# Heart-shaped-LED.net
KiCad netlist of a schematic drawn in EAGLE
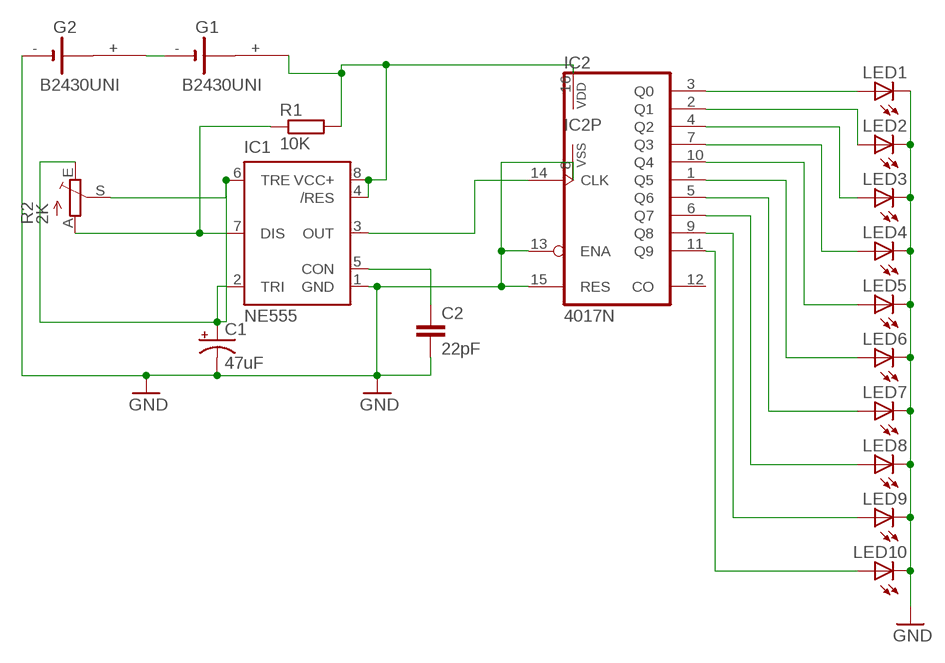
[diagram p0: schematic, sheet 1]

(export (version "E")
  (design (tool "Eeschema 10.0.6"))
  (components
    (comp (ref "C1")
      (value "47uF")
      (footprint "eagle-import:B45181A")
      (libsource (lib "eagle-import") (part "CPOL-USB45181A"))
    )
    (comp (ref "C2")
      (value "22pF")
      (footprint "eagle-import:C025-024X044")
      (libsource (lib "eagle-import") (part "C-EU025-024X044"))
    )
    (comp (ref "G1")
      (value "B2430UNI")
      (footprint "eagle-import:B2430UNI")
      (libsource (lib "eagle-import") (part "B2430UNI"))
    )
    (comp (ref "G2")
      (value "B2430UNI")
      (footprint "eagle-import:B2430UNI")
      (libsource (lib "eagle-import") (part "B2430UNI"))
    )
    (comp (ref "IC1")
      (value "NE555")
      (footprint "eagle-import:DIL-08")
      (fields (field (name "MF") "Arrow Electronics") (field (name "MPN") "NE555N"))
      (libsource (lib "eagle-import") (part "NE555"))
    )
    (comp (ref "IC2")
      (value "4017N")
      (footprint "eagle-import:DIL16")
      (fields (field (name "SPICEPREFIX") "X"))
      (libsource (lib "eagle-import") (part "4017N"))
    )
    (comp (ref "LED1")
      (value "LED5MM")
      (footprint "eagle-import:LED5MM")
      (libsource (lib "eagle-import") (part "LED5MM"))
    )
    (comp (ref "LED2")
      (value "LED5MM")
      (footprint "eagle-import:LED5MM")
      (libsource (lib "eagle-import") (part "LED5MM"))
    )
    (comp (ref "LED3")
      (value "LED5MM")
      (footprint "eagle-import:LED5MM")
      (libsource (lib "eagle-import") (part "LED5MM"))
    )
    (comp (ref "LED4")
      (value "LED5MM")
      (footprint "eagle-import:LED5MM")
      (libsource (lib "eagle-import") (part "LED5MM"))
    )
    (comp (ref "LED5")
      (value "LED5MM")
      (footprint "eagle-import:LED5MM")
      (libsource (lib "eagle-import") (part "LED5MM"))
    )
    (comp (ref "LED6")
      (value "LED5MM")
      (footprint "eagle-import:LED5MM")
      (libsource (lib "eagle-import") (part "LED5MM"))
    )
    (comp (ref "LED7")
      (value "LED5MM")
      (footprint "eagle-import:LED5MM")
      (libsource (lib "eagle-import") (part "LED5MM"))
    )
    (comp (ref "LED8")
      (value "LED5MM")
      (footprint "eagle-import:LED5MM")
      (libsource (lib "eagle-import") (part "LED5MM"))
    )
    (comp (ref "LED9")
      (value "LED5MM")
      (footprint "eagle-import:LED5MM")
      (libsource (lib "eagle-import") (part "LED5MM"))
    )
    (comp (ref "LED10")
      (value "LED5MM")
      (footprint "eagle-import:LED5MM")
      (libsource (lib "eagle-import") (part "LED5MM"))
    )
    (comp (ref "R1")
      (value "10K")
      (footprint "eagle-import:0207_7")
      (libsource (lib "eagle-import") (part "R-EU_0207/7"))
    )
    (comp (ref "R2")
      (value "2K")
      (footprint "eagle-import:CA9V")
      (libsource (lib "eagle-import") (part "TRIM_EU-CA9V"))
    )
  )
  (nets
    (net (code "1") (name "GND") (class "Default")
      (node (ref "C1") (pin "-") (pinfunction "-_-") (pintype "passive"))
      (node (ref "C2") (pin "2") (pinfunction "2_2") (pintype "passive"))
      (node (ref "G2") (pin "-") (pinfunction "-_-") (pintype "passive"))
      (node (ref "IC1") (pin "1") (pinfunction "GND_1") (pintype "power_in"))
      (node (ref "IC2") (pin "13") (pinfunction "ENA_13") (pintype "input"))
      (node (ref "IC2") (pin "15") (pinfunction "RES_15") (pintype "input"))
      (node (ref "IC2") (pin "8") (pinfunction "VSS_8") (pintype "power_in"))
      (node (ref "LED1") (pin "K") (pinfunction "C_K") (pintype "passive"))
      (node (ref "LED10") (pin "K") (pinfunction "C_K") (pintype "passive"))
      (node (ref "LED2") (pin "K") (pinfunction "C_K") (pintype "passive"))
      (node (ref "LED3") (pin "K") (pinfunction "C_K") (pintype "passive"))
      (node (ref "LED4") (pin "K") (pinfunction "C_K") (pintype "passive"))
      (node (ref "LED5") (pin "K") (pinfunction "C_K") (pintype "passive"))
      (node (ref "LED6") (pin "K") (pinfunction "C_K") (pintype "passive"))
      (node (ref "LED7") (pin "K") (pinfunction "C_K") (pintype "passive"))
      (node (ref "LED8") (pin "K") (pinfunction "C_K") (pintype "passive"))
      (node (ref "LED9") (pin "K") (pinfunction "C_K") (pintype "passive"))
    )
    (net (code "2") (name "Net-(G1-Pad-)") (class "Default")
      (node (ref "G1") (pin "-") (pinfunction "-_-") (pintype "passive"))
      (node (ref "G2") (pin "+") (pinfunction "+_+") (pintype "passive"))
    )
    (net (code "3") (name "Net-(IC1-CON)") (class "Default")
      (node (ref "C2") (pin "1") (pinfunction "1_1") (pintype "passive"))
      (node (ref "IC1") (pin "5") (pinfunction "CON_5") (pintype "input"))
    )
    (net (code "4") (name "Net-(IC1-DIS)") (class "Default")
      (node (ref "IC1") (pin "7") (pinfunction "DIS_7") (pintype "input"))
      (node (ref "R1") (pin "1") (pinfunction "1_1") (pintype "passive"))
      (node (ref "R2") (pin "A") (pinfunction "A_A") (pintype "passive"))
    )
    (net (code "5") (name "Net-(IC1-OUT)") (class "Default")
      (node (ref "IC1") (pin "3") (pinfunction "OUT_3") (pintype "output"))
      (node (ref "IC2") (pin "14") (pinfunction "CLK_14") (pintype "input"))
    )
    (net (code "6") (name "Net-(IC1-TRE)") (class "Default")
      (node (ref "C1") (pin "+") (pinfunction "+_+") (pintype "passive"))
      (node (ref "IC1") (pin "2") (pinfunction "TRI_2") (pintype "input"))
      (node (ref "IC1") (pin "6") (pinfunction "TRE_6") (pintype "input"))
      (node (ref "R2") (pin "E") (pinfunction "E_E") (pintype "passive"))
      (node (ref "R2") (pin "S") (pinfunction "S_S") (pintype "passive"))
    )
    (net (code "7") (name "Net-(IC1-VCC+)") (class "Default")
      (node (ref "G1") (pin "+") (pinfunction "+_+") (pintype "passive"))
      (node (ref "IC1") (pin "4") (pinfunction "/RES_4") (pintype "input"))
      (node (ref "IC1") (pin "8") (pinfunction "VCC+_8") (pintype "power_in"))
      (node (ref "IC2") (pin "16") (pinfunction "VDD_16") (pintype "power_in"))
      (node (ref "R1") (pin "2") (pinfunction "2_2") (pintype "passive"))
    )
    (net (code "8") (name "Net-(IC2A-Q0)") (class "Default")
      (node (ref "IC2") (pin "3") (pinfunction "Q0_3") (pintype "output"))
      (node (ref "LED1") (pin "A") (pinfunction "A_A") (pintype "passive"))
    )
    (net (code "9") (name "Net-(IC2A-Q1)") (class "Default")
      (node (ref "IC2") (pin "2") (pinfunction "Q1_2") (pintype "output"))
      (node (ref "LED2") (pin "A") (pinfunction "A_A") (pintype "passive"))
    )
    (net (code "10") (name "Net-(IC2A-Q2)") (class "Default")
      (node (ref "IC2") (pin "4") (pinfunction "Q2_4") (pintype "output"))
      (node (ref "LED3") (pin "A") (pinfunction "A_A") (pintype "passive"))
    )
    (net (code "11") (name "Net-(IC2A-Q3)") (class "Default")
      (node (ref "IC2") (pin "7") (pinfunction "Q3_7") (pintype "output"))
      (node (ref "LED4") (pin "A") (pinfunction "A_A") (pintype "passive"))
    )
    (net (code "12") (name "Net-(IC2A-Q4)") (class "Default")
      (node (ref "IC2") (pin "10") (pinfunction "Q4_10") (pintype "output"))
      (node (ref "LED5") (pin "A") (pinfunction "A_A") (pintype "passive"))
    )
    (net (code "13") (name "Net-(IC2A-Q5)") (class "Default")
      (node (ref "IC2") (pin "1") (pinfunction "Q5_1") (pintype "output"))
      (node (ref "LED6") (pin "A") (pinfunction "A_A") (pintype "passive"))
    )
    (net (code "14") (name "Net-(IC2A-Q6)") (class "Default")
      (node (ref "IC2") (pin "5") (pinfunction "Q6_5") (pintype "output"))
      (node (ref "LED7") (pin "A") (pinfunction "A_A") (pintype "passive"))
    )
    (net (code "15") (name "Net-(IC2A-Q7)") (class "Default")
      (node (ref "IC2") (pin "6") (pinfunction "Q7_6") (pintype "output"))
      (node (ref "LED8") (pin "A") (pinfunction "A_A") (pintype "passive"))
    )
    (net (code "16") (name "Net-(IC2A-Q8)") (class "Default")
      (node (ref "IC2") (pin "9") (pinfunction "Q8_9") (pintype "output"))
      (node (ref "LED9") (pin "A") (pinfunction "A_A") (pintype "passive"))
    )
    (net (code "17") (name "Net-(IC2A-Q9)") (class "Default")
      (node (ref "IC2") (pin "11") (pinfunction "Q9_11") (pintype "output"))
      (node (ref "LED10") (pin "A") (pinfunction "A_A") (pintype "passive"))
    )
    (net (code "18") (name "unconnected-(G1-+-Pad+@1)") (class "Default")
      (node (ref "G1") (pin "+@1") (pinfunction "+_+@1") (pintype "passive"))
    )
    (net (code "19") (name "unconnected-(G1-+-Pad+@2)") (class "Default")
      (node (ref "G1") (pin "+@2") (pinfunction "+_+@2") (pintype "passive"))
    )
    (net (code "20") (name "unconnected-(G1-+-Pad+@3)") (class "Default")
      (node (ref "G1") (pin "+@3") (pinfunction "+_+@3") (pintype "passive"))
    )
    (net (code "21") (name "unconnected-(G1-+-Pad+@4)") (class "Default")
      (node (ref "G1") (pin "+@4") (pinfunction "+_+@4") (pintype "passive"))
    )
    (net (code "22") (name "unconnected-(G1---Pad-@1)") (class "Default")
      (node (ref "G1") (pin "-@1") (pinfunction "-_-@1") (pintype "passive"))
    )
    (net (code "23") (name "unconnected-(G2-+-Pad+@1)") (class "Default")
      (node (ref "G2") (pin "+@1") (pinfunction "+_+@1") (pintype "passive"))
    )
    (net (code "24") (name "unconnected-(G2-+-Pad+@2)") (class "Default")
      (node (ref "G2") (pin "+@2") (pinfunction "+_+@2") (pintype "passive"))
    )
    (net (code "25") (name "unconnected-(G2-+-Pad+@3)") (class "Default")
      (node (ref "G2") (pin "+@3") (pinfunction "+_+@3") (pintype "passive"))
    )
    (net (code "26") (name "unconnected-(G2-+-Pad+@4)") (class "Default")
      (node (ref "G2") (pin "+@4") (pinfunction "+_+@4") (pintype "passive"))
    )
    (net (code "27") (name "unconnected-(G2---Pad-@1)") (class "Default")
      (node (ref "G2") (pin "-@1") (pinfunction "-_-@1") (pintype "passive"))
    )
    (net (code "28") (name "unconnected-(IC2A-CO-Pad12)") (class "Default")
      (node (ref "IC2") (pin "12") (pinfunction "CO_12") (pintype "output"))
    )
  )
)
